# ESP8266-IoT_Expansion.net
KiCad netlist of a schematic drawn in EAGLE
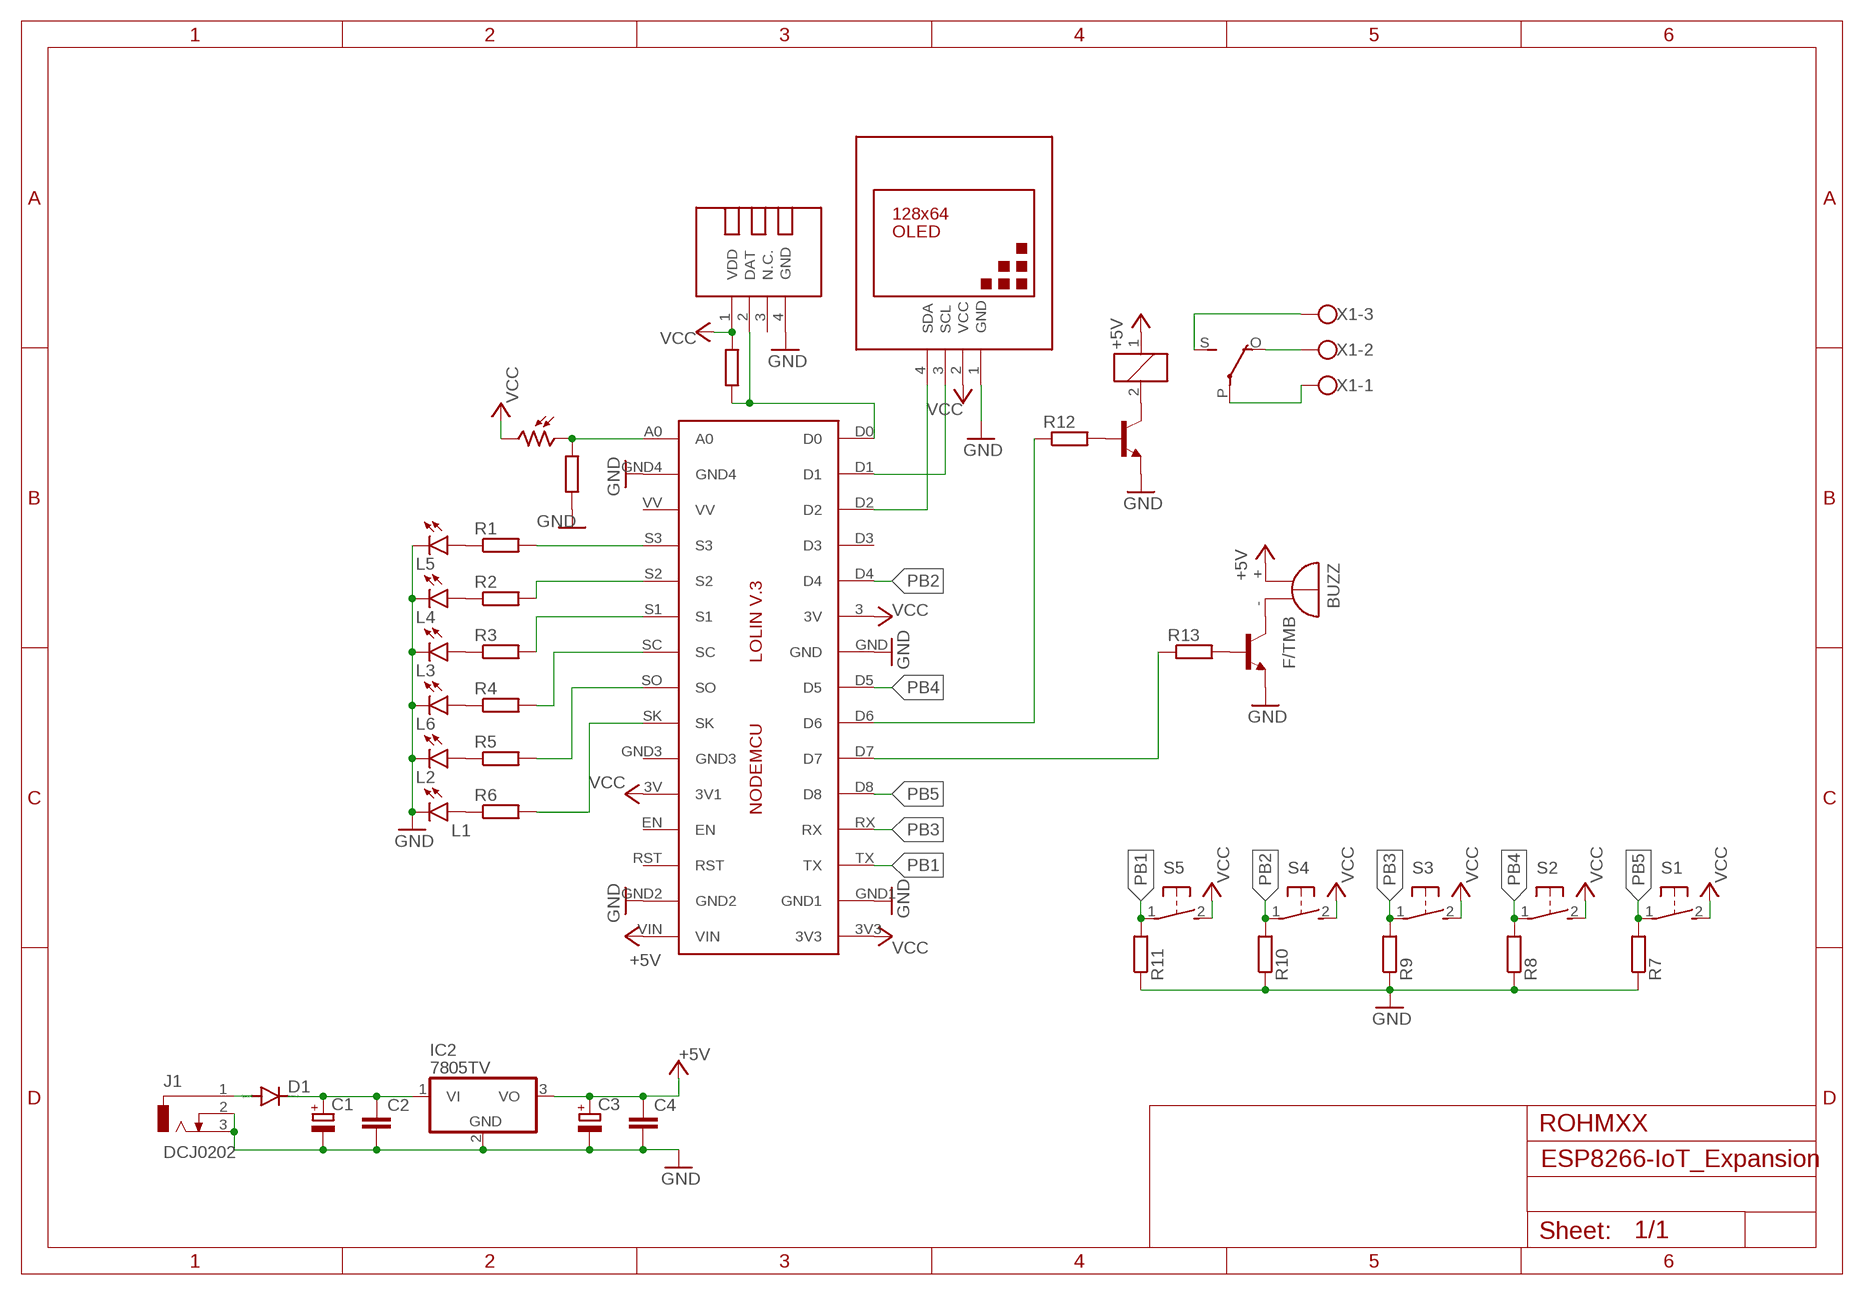
[diagram p0: schematic, sheet 1]

(export (version "E")
  (design (tool "Eeschema 10.0.6"))
  (components
    (comp (ref "BUZZ")
      (value "F/TMB")
      (footprint "eagle-import:F_TMB")
      (libsource (lib "eagle-import") (part "F/TMB"))
    )
    (comp (ref "C1")
      (value "CPOL-EUE5-10.5")
      (footprint "eagle-import:E5-10,5")
      (libsource (lib "eagle-import") (part "CPOL-EUE5-10.5"))
    )
    (comp (ref "C2")
      (value "C-EU075-032X103")
      (footprint "eagle-import:C075-032X103")
      (libsource (lib "eagle-import") (part "C-EU075-032X103"))
    )
    (comp (ref "C3")
      (value "CPOL-EUE5-10.5")
      (footprint "eagle-import:E5-10,5")
      (libsource (lib "eagle-import") (part "CPOL-EUE5-10.5"))
    )
    (comp (ref "C4")
      (value "C-EU075-032X103")
      (footprint "eagle-import:C075-032X103")
      (libsource (lib "eagle-import") (part "C-EU075-032X103"))
    )
    (comp (ref "D1")
      (value "1N4007")
      (footprint "eagle-import:DO35-7")
      (libsource (lib "eagle-import") (part "1N4148DO35-7"))
    )
    (comp (ref "DHT-11")
      (value "TEMP-HUM-SENSOR-DHT11")
      (footprint "eagle-import:TEMP-HUM-SENSOR-DHT11")
      (libsource (lib "eagle-import") (part "TEMP-HUM-SENSOR-DHT11"))
    )
    (comp (ref "IC1")
      (value "LOLINV3")
      (footprint "eagle-import:LOLINV3")
      (libsource (lib "eagle-import") (part "LOLINV3"))
    )
    (comp (ref "IC2")
      (value "7805TV")
      (footprint "eagle-import:TO220V")
      (libsource (lib "eagle-import") (part "78TV05"))
    )
    (comp (ref "J1")
      (value "DCJ0202")
      (footprint "eagle-import:DCJ0202")
      (libsource (lib "eagle-import") (part "DCJ0202"))
    )
    (comp (ref "K1")
      (value "G5LE")
      (footprint "eagle-import:G5LE")
      (libsource (lib "eagle-import") (part "G5LE"))
    )
    (comp (ref "L1")
      (value "LED3MM")
      (footprint "eagle-import:LED3MM")
      (libsource (lib "eagle-import") (part "LED3MM"))
    )
    (comp (ref "L2")
      (value "LED3MM")
      (footprint "eagle-import:LED3MM")
      (libsource (lib "eagle-import") (part "LED3MM"))
    )
    (comp (ref "L3")
      (value "LED3MM")
      (footprint "eagle-import:LED3MM")
      (libsource (lib "eagle-import") (part "LED3MM"))
    )
    (comp (ref "L4")
      (value "LED3MM")
      (footprint "eagle-import:LED3MM")
      (libsource (lib "eagle-import") (part "LED3MM"))
    )
    (comp (ref "L5")
      (value "LED3MM")
      (footprint "eagle-import:LED3MM")
      (libsource (lib "eagle-import") (part "LED3MM"))
    )
    (comp (ref "L6")
      (value "LED3MM")
      (footprint "eagle-import:LED3MM")
      (libsource (lib "eagle-import") (part "LED3MM"))
    )
    (comp (ref "LDR")
      (value "V1060_21")
      (footprint "eagle-import:TO-5_V10")
      (libsource (lib "eagle-import") (part "?1060V_21"))
    )
    (comp (ref "R1")
      (value "R-EU_0207/7")
      (footprint "eagle-import:0207_7")
      (libsource (lib "eagle-import") (part "R-EU_0207/7"))
    )
    (comp (ref "R2")
      (value "R-EU_0207/7")
      (footprint "eagle-import:0207_7")
      (libsource (lib "eagle-import") (part "R-EU_0207/7"))
    )
    (comp (ref "R3")
      (value "R-EU_0207/7")
      (footprint "eagle-import:0207_7")
      (libsource (lib "eagle-import") (part "R-EU_0207/7"))
    )
    (comp (ref "R4")
      (value "R-EU_0207/7")
      (footprint "eagle-import:0207_7")
      (libsource (lib "eagle-import") (part "R-EU_0207/7"))
    )
    (comp (ref "R5")
      (value "R-EU_0207/7")
      (footprint "eagle-import:0207_7")
      (libsource (lib "eagle-import") (part "R-EU_0207/7"))
    )
    (comp (ref "R6")
      (value "R-EU_0207/7")
      (footprint "eagle-import:0207_7")
      (libsource (lib "eagle-import") (part "R-EU_0207/7"))
    )
    (comp (ref "R7")
      (value "R-EU_0207/7")
      (footprint "eagle-import:0207_7")
      (libsource (lib "eagle-import") (part "R-EU_0207/7"))
    )
    (comp (ref "R8")
      (value "R-EU_0207/7")
      (footprint "eagle-import:0207_7")
      (libsource (lib "eagle-import") (part "R-EU_0207/7"))
    )
    (comp (ref "R9")
      (value "R-EU_0207/7")
      (footprint "eagle-import:0207_7")
      (libsource (lib "eagle-import") (part "R-EU_0207/7"))
    )
    (comp (ref "R10")
      (value "R-EU_0207/7")
      (footprint "eagle-import:0207_7")
      (libsource (lib "eagle-import") (part "R-EU_0207/7"))
    )
    (comp (ref "R11")
      (value "R-EU_0207/7")
      (footprint "eagle-import:0207_7")
      (libsource (lib "eagle-import") (part "R-EU_0207/7"))
    )
    (comp (ref "R12")
      (value "R-EU_0207/7")
      (footprint "eagle-import:0207_7")
      (libsource (lib "eagle-import") (part "R-EU_0207/7"))
    )
    (comp (ref "R13")
      (value "R-EU_0207/7")
      (footprint "eagle-import:0207_7")
      (libsource (lib "eagle-import") (part "R-EU_0207/7"))
    )
    (comp (ref "R14")
      (value "R-EU_0207/7")
      (footprint "eagle-import:0207_7")
      (libsource (lib "eagle-import") (part "R-EU_0207/7"))
    )
    (comp (ref "R15")
      (value "R-EU_0207/7")
      (footprint "eagle-import:0207_7")
      (libsource (lib "eagle-import") (part "R-EU_0207/7"))
    )
    (comp (ref "S1")
      (value "DTS-3")
      (footprint "eagle-import:DTS-3")
      (libsource (lib "eagle-import") (part "DTS-3"))
    )
    (comp (ref "S2")
      (value "DTS-3")
      (footprint "eagle-import:DTS-3")
      (libsource (lib "eagle-import") (part "DTS-3"))
    )
    (comp (ref "S3")
      (value "DTS-3")
      (footprint "eagle-import:DTS-3")
      (libsource (lib "eagle-import") (part "DTS-3"))
    )
    (comp (ref "S4")
      (value "DTS-3")
      (footprint "eagle-import:DTS-3")
      (libsource (lib "eagle-import") (part "DTS-3"))
    )
    (comp (ref "S5")
      (value "DTS-3")
      (footprint "eagle-import:DTS-3")
      (libsource (lib "eagle-import") (part "DTS-3"))
    )
    (comp (ref "T1")
      (value "2N3904")
      (footprint "eagle-import:TO92")
      (libsource (lib "eagle-import") (part "2N3904"))
    )
    (comp (ref "T2")
      (value "2N3904")
      (footprint "eagle-import:TO92")
      (libsource (lib "eagle-import") (part "2N3904"))
    )
    (comp (ref "U$1")
      (value "DISPLAY-OLED-128X64-I2C")
      (footprint "eagle-import:DISPLAY-OLED-128X64-I2C")
      (libsource (lib "eagle-import") (part "DISPLAY-OLED-128X64-I2C"))
    )
    (comp (ref "X1")
      (value "W237-103")
      (footprint "eagle-import:W237-103")
      (fields (field (name "MPN") "237-103"))
      (libsource (lib "eagle-import") (part "W237-103"))
    )
  )
  (nets
    (net (code "1") (name "+5V") (class "Default")
      (node (ref "BUZZ") (pin "+") (pinfunction "+_+") (pintype "passive"))
      (node (ref "C3") (pin "+") (pinfunction "+_+") (pintype "passive"))
      (node (ref "C4") (pin "1") (pinfunction "1_1") (pintype "passive"))
      (node (ref "IC1") (pin "VIN") (pinfunction "VIN_VIN") (pintype "bidirectional"))
      (node (ref "IC2") (pin "3") (pinfunction "VO_3") (pintype "passive"))
      (node (ref "K1") (pin "1") (pinfunction "1_1") (pintype "passive"))
    )
    (net (code "2") (name "GND") (class "Default")
      (node (ref "C1") (pin "-") (pinfunction "-_-") (pintype "passive"))
      (node (ref "C2") (pin "2") (pinfunction "2_2") (pintype "passive"))
      (node (ref "C3") (pin "-") (pinfunction "-_-") (pintype "passive"))
      (node (ref "C4") (pin "2") (pinfunction "2_2") (pintype "passive"))
      (node (ref "DHT-11") (pin "4") (pinfunction "GND_4") (pintype "power_in"))
      (node (ref "IC1") (pin "GND") (pinfunction "GND_GND") (pintype "bidirectional"))
      (node (ref "IC1") (pin "GND1") (pinfunction "GND1_GND1") (pintype "bidirectional"))
      (node (ref "IC1") (pin "GND2") (pinfunction "GND2_GND2") (pintype "bidirectional"))
      (node (ref "IC1") (pin "GND4") (pinfunction "GND4_GND4") (pintype "bidirectional"))
      (node (ref "IC2") (pin "2") (pinfunction "GND_2") (pintype "passive"))
      (node (ref "J1") (pin "2") (pinfunction "2_2") (pintype "passive"))
      (node (ref "J1") (pin "3") (pinfunction "3_3") (pintype "passive"))
      (node (ref "L1") (pin "K") (pinfunction "C_K") (pintype "passive"))
      (node (ref "L2") (pin "K") (pinfunction "C_K") (pintype "passive"))
      (node (ref "L3") (pin "K") (pinfunction "C_K") (pintype "passive"))
      (node (ref "L4") (pin "K") (pinfunction "C_K") (pintype "passive"))
      (node (ref "L5") (pin "K") (pinfunction "C_K") (pintype "passive"))
      (node (ref "L6") (pin "K") (pinfunction "C_K") (pintype "passive"))
      (node (ref "R10") (pin "1") (pinfunction "1_1") (pintype "passive"))
      (node (ref "R11") (pin "1") (pinfunction "1_1") (pintype "passive"))
      (node (ref "R14") (pin "1") (pinfunction "1_1") (pintype "passive"))
      (node (ref "R7") (pin "1") (pinfunction "1_1") (pintype "passive"))
      (node (ref "R8") (pin "1") (pinfunction "1_1") (pintype "passive"))
      (node (ref "R9") (pin "1") (pinfunction "1_1") (pintype "passive"))
      (node (ref "T1") (pin "3") (pinfunction "E_3") (pintype "passive"))
      (node (ref "T2") (pin "3") (pinfunction "E_3") (pintype "passive"))
      (node (ref "U$1") (pin "1") (pinfunction "GND_1") (pintype "power_in"))
    )
    (net (code "3") (name "Net-(D1-PadA)") (class "Default")
      (node (ref "D1") (pin "A") (pinfunction "A_A") (pintype "passive"))
      (node (ref "J1") (pin "1") (pinfunction "1_1") (pintype "passive"))
    )
    (net (code "4") (name "Net-(DHT-11-DAT)") (class "Default")
      (node (ref "DHT-11") (pin "2") (pinfunction "DAT_2") (pintype "bidirectional"))
      (node (ref "IC1") (pin "D0") (pinfunction "D0_D0") (pintype "bidirectional"))
      (node (ref "R15") (pin "2") (pinfunction "2_2") (pintype "passive"))
    )
    (net (code "5") (name "Net-(IC1-PadA0)") (class "Default")
      (node (ref "IC1") (pin "A0") (pinfunction "A0_A0") (pintype "bidirectional"))
      (node (ref "LDR") (pin "1") (pinfunction "1_1") (pintype "passive"))
      (node (ref "R14") (pin "2") (pinfunction "2_2") (pintype "passive"))
    )
    (net (code "6") (name "Net-(IC1-PadD6)") (class "Default")
      (node (ref "IC1") (pin "D6") (pinfunction "D6_D6") (pintype "bidirectional"))
      (node (ref "R12") (pin "1") (pinfunction "1_1") (pintype "passive"))
    )
    (net (code "7") (name "Net-(IC1-PadD7)") (class "Default")
      (node (ref "IC1") (pin "D7") (pinfunction "D7_D7") (pintype "bidirectional"))
      (node (ref "R13") (pin "1") (pinfunction "1_1") (pintype "passive"))
    )
    (net (code "8") (name "Net-(IC1-PadS1)") (class "Default")
      (node (ref "IC1") (pin "S1") (pinfunction "S1_S1") (pintype "bidirectional"))
      (node (ref "R3") (pin "2") (pinfunction "2_2") (pintype "passive"))
    )
    (net (code "9") (name "Net-(IC1-PadS2)") (class "Default")
      (node (ref "IC1") (pin "S2") (pinfunction "S2_S2") (pintype "bidirectional"))
      (node (ref "R2") (pin "2") (pinfunction "2_2") (pintype "passive"))
    )
    (net (code "10") (name "Net-(IC1-PadS3)") (class "Default")
      (node (ref "IC1") (pin "S3") (pinfunction "S3_S3") (pintype "bidirectional"))
      (node (ref "R1") (pin "2") (pinfunction "2_2") (pintype "passive"))
    )
    (net (code "11") (name "Net-(IC1-PadSC)") (class "Default")
      (node (ref "IC1") (pin "SC") (pinfunction "SC_SC") (pintype "bidirectional"))
      (node (ref "R4") (pin "2") (pinfunction "2_2") (pintype "passive"))
    )
    (net (code "12") (name "Net-(IC1-PadSK)") (class "Default")
      (node (ref "IC1") (pin "SK") (pinfunction "SK_SK") (pintype "bidirectional"))
      (node (ref "R6") (pin "2") (pinfunction "2_2") (pintype "passive"))
    )
    (net (code "13") (name "Net-(IC1-PadSO)") (class "Default")
      (node (ref "IC1") (pin "SO") (pinfunction "SO_SO") (pintype "bidirectional"))
      (node (ref "R5") (pin "2") (pinfunction "2_2") (pintype "passive"))
    )
    (net (code "14") (name "Net-(IC2-VI)") (class "Default")
      (node (ref "C1") (pin "+") (pinfunction "+_+") (pintype "passive"))
      (node (ref "C2") (pin "1") (pinfunction "1_1") (pintype "passive"))
      (node (ref "D1") (pin "C") (pinfunction "C_C") (pintype "passive"))
      (node (ref "IC2") (pin "1") (pinfunction "VI_1") (pintype "input"))
    )
    (net (code "15") (name "Net-(L1-PadA)") (class "Default")
      (node (ref "L1") (pin "A") (pinfunction "A_A") (pintype "passive"))
      (node (ref "R6") (pin "1") (pinfunction "1_1") (pintype "passive"))
    )
    (net (code "16") (name "Net-(L2-PadA)") (class "Default")
      (node (ref "L2") (pin "A") (pinfunction "A_A") (pintype "passive"))
      (node (ref "R5") (pin "1") (pinfunction "1_1") (pintype "passive"))
    )
    (net (code "17") (name "Net-(L3-PadA)") (class "Default")
      (node (ref "L3") (pin "A") (pinfunction "A_A") (pintype "passive"))
      (node (ref "R3") (pin "1") (pinfunction "1_1") (pintype "passive"))
    )
    (net (code "18") (name "Net-(L4-PadA)") (class "Default")
      (node (ref "L4") (pin "A") (pinfunction "A_A") (pintype "passive"))
      (node (ref "R2") (pin "1") (pinfunction "1_1") (pintype "passive"))
    )
    (net (code "19") (name "Net-(L5-PadA)") (class "Default")
      (node (ref "L5") (pin "A") (pinfunction "A_A") (pintype "passive"))
      (node (ref "R1") (pin "1") (pinfunction "1_1") (pintype "passive"))
    )
    (net (code "20") (name "Net-(L6-PadA)") (class "Default")
      (node (ref "L6") (pin "A") (pinfunction "A_A") (pintype "passive"))
      (node (ref "R4") (pin "1") (pinfunction "1_1") (pintype "passive"))
    )
    (net (code "21") (name "Net-(T1-B)") (class "Default")
      (node (ref "R13") (pin "2") (pinfunction "2_2") (pintype "passive"))
      (node (ref "T1") (pin "2") (pinfunction "B_2") (pintype "passive"))
    )
    (net (code "22") (name "Net-(T1-C)") (class "Default")
      (node (ref "BUZZ") (pin "-") (pinfunction "-_-") (pintype "passive"))
      (node (ref "T1") (pin "1") (pinfunction "C_1") (pintype "passive"))
    )
    (net (code "23") (name "Net-(T2-B)") (class "Default")
      (node (ref "R12") (pin "2") (pinfunction "2_2") (pintype "passive"))
      (node (ref "T2") (pin "2") (pinfunction "B_2") (pintype "passive"))
    )
    (net (code "24") (name "Net-(T2-C)") (class "Default")
      (node (ref "K1") (pin "2") (pinfunction "2_2") (pintype "passive"))
      (node (ref "T2") (pin "1") (pinfunction "C_1") (pintype "passive"))
    )
    (net (code "25") (name "Net-(U$1-SCL)") (class "Default")
      (node (ref "IC1") (pin "D1") (pinfunction "D1_D1") (pintype "bidirectional"))
      (node (ref "U$1") (pin "3") (pinfunction "SCL_3") (pintype "bidirectional"))
    )
    (net (code "26") (name "Net-(U$1-SDA)") (class "Default")
      (node (ref "IC1") (pin "D2") (pinfunction "D2_D2") (pintype "bidirectional"))
      (node (ref "U$1") (pin "4") (pinfunction "SDA_4") (pintype "bidirectional"))
    )
    (net (code "27") (name "Net-(X1A-KL)") (class "Default")
      (node (ref "K1") (pin "P") (pinfunction "P_P") (pintype "passive"))
      (node (ref "X1") (pin "1") (pinfunction "KL_1") (pintype "passive"))
    )
    (net (code "28") (name "Net-(X1B-KL)") (class "Default")
      (node (ref "K1") (pin "O") (pinfunction "O_O") (pintype "passive"))
      (node (ref "X1") (pin "2") (pinfunction "KL_2") (pintype "passive"))
    )
    (net (code "29") (name "Net-(X1C-KL)") (class "Default")
      (node (ref "K1") (pin "S") (pinfunction "S_S") (pintype "passive"))
      (node (ref "X1") (pin "3") (pinfunction "KL_3") (pintype "passive"))
    )
    (net (code "30") (name "PB1") (class "Default")
      (node (ref "IC1") (pin "TX") (pinfunction "TX_TX") (pintype "bidirectional"))
      (node (ref "R11") (pin "2") (pinfunction "2_2") (pintype "passive"))
      (node (ref "S5") (pin "1") (pinfunction "1_1") (pintype "passive"))
    )
    (net (code "31") (name "PB2") (class "Default")
      (node (ref "IC1") (pin "D4") (pinfunction "D4_D4") (pintype "bidirectional"))
      (node (ref "R10") (pin "2") (pinfunction "2_2") (pintype "passive"))
      (node (ref "S4") (pin "1") (pinfunction "1_1") (pintype "passive"))
    )
    (net (code "32") (name "PB3") (class "Default")
      (node (ref "IC1") (pin "RX") (pinfunction "RX_RX") (pintype "bidirectional"))
      (node (ref "R9") (pin "2") (pinfunction "2_2") (pintype "passive"))
      (node (ref "S3") (pin "1") (pinfunction "1_1") (pintype "passive"))
    )
    (net (code "33") (name "PB4") (class "Default")
      (node (ref "IC1") (pin "D5") (pinfunction "D5_D5") (pintype "bidirectional"))
      (node (ref "R8") (pin "2") (pinfunction "2_2") (pintype "passive"))
      (node (ref "S2") (pin "1") (pinfunction "1_1") (pintype "passive"))
    )
    (net (code "34") (name "PB5") (class "Default")
      (node (ref "IC1") (pin "D8") (pinfunction "D8_D8") (pintype "bidirectional"))
      (node (ref "R7") (pin "2") (pinfunction "2_2") (pintype "passive"))
      (node (ref "S1") (pin "1") (pinfunction "1_1") (pintype "passive"))
    )
    (net (code "35") (name "VCC") (class "Default")
      (node (ref "DHT-11") (pin "1") (pinfunction "VDD_1") (pintype "power_in"))
      (node (ref "IC1") (pin "3") (pinfunction "3V_3") (pintype "bidirectional"))
      (node (ref "IC1") (pin "3V") (pinfunction "3V1_3V") (pintype "bidirectional"))
      (node (ref "IC1") (pin "3V3") (pinfunction "3V3_3V3") (pintype "bidirectional"))
      (node (ref "LDR") (pin "2") (pinfunction "2_2") (pintype "passive"))
      (node (ref "R15") (pin "1") (pinfunction "1_1") (pintype "passive"))
      (node (ref "S1") (pin "2") (pinfunction "2_2") (pintype "passive"))
      (node (ref "S2") (pin "2") (pinfunction "2_2") (pintype "passive"))
      (node (ref "S3") (pin "2") (pinfunction "2_2") (pintype "passive"))
      (node (ref "S4") (pin "2") (pinfunction "2_2") (pintype "passive"))
      (node (ref "S5") (pin "2") (pinfunction "2_2") (pintype "passive"))
      (node (ref "U$1") (pin "2") (pinfunction "VCC_2") (pintype "power_in"))
    )
    (net (code "36") (name "unconnected-(DHT-11-N.C.-Pad3)") (class "Default")
      (node (ref "DHT-11") (pin "3") (pinfunction "N.C._3") (pintype "passive"))
    )
    (net (code "37") (name "unconnected-(IC1-PadD3)") (class "Default")
      (node (ref "IC1") (pin "D3") (pinfunction "D3_D3") (pintype "bidirectional"))
    )
    (net (code "38") (name "unconnected-(IC1-PadEN)") (class "Default")
      (node (ref "IC1") (pin "EN") (pinfunction "EN_EN") (pintype "bidirectional"))
    )
    (net (code "39") (name "unconnected-(IC1-PadGND3)") (class "Default")
      (node (ref "IC1") (pin "GND3") (pinfunction "GND3_GND3") (pintype "bidirectional"))
    )
    (net (code "40") (name "unconnected-(IC1-PadRST)") (class "Default")
      (node (ref "IC1") (pin "RST") (pinfunction "RST_RST") (pintype "bidirectional"))
    )
    (net (code "41") (name "unconnected-(IC1-PadVV)") (class "Default")
      (node (ref "IC1") (pin "VV") (pinfunction "VV_VV") (pintype "bidirectional"))
    )
  )
)
